# esp-sensor_01.net
KiCad netlist of a schematic drawn in EAGLE
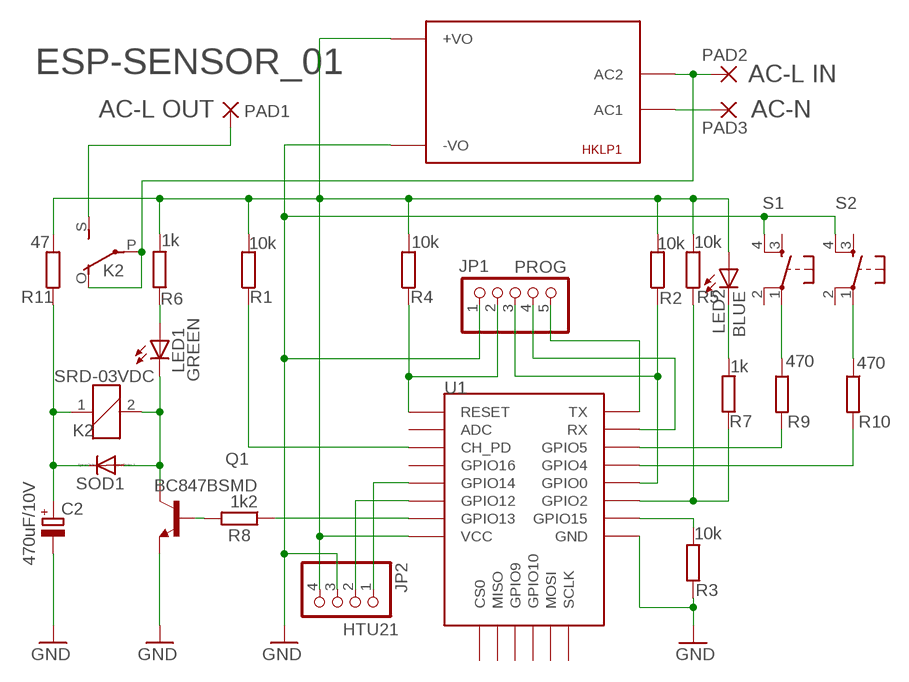
[diagram p0: schematic, sheet 1]

(export (version "E")
  (design (tool "Eeschema 10.0.6"))
  (components
    (comp (ref "C2")
      (value "470uF/10V")
      (footprint "eagle-import:E3,5-8-B")
      (libsource (lib "eagle-import") (part "CPOL-EUE3,5-8-B"))
    )
    (comp (ref "HKLP1")
      (value "HKLPM01")
      (footprint "eagle-import:HKLPM01")
      (libsource (lib "eagle-import") (part "HKLPM01"))
    )
    (comp (ref "JP1")
      (value "PROG")
      (footprint "eagle-import:1X05-2B")
      (libsource (lib "eagle-import") (part "PINHD-1X51X05-2B"))
    )
    (comp (ref "JP2")
      (value "HTU21")
      (footprint "eagle-import:1X04")
      (libsource (lib "eagle-import") (part "PINHD-1X4"))
    )
    (comp (ref "K2")
      (value "SRD-03VDC")
      (footprint "eagle-import:G5L-2B")
      (libsource (lib "eagle-import") (part "G5L-2B"))
    )
    (comp (ref "LED1")
      (value "GREEN")
      (footprint "eagle-import:LED3MM-B")
      (libsource (lib "eagle-import") (part "LEDB"))
    )
    (comp (ref "LED2")
      (value "BLUE")
      (footprint "eagle-import:LED3MM-B")
      (libsource (lib "eagle-import") (part "LEDB"))
    )
    (comp (ref "PAD1")
      (value "3,17/1,1")
      (footprint "eagle-import:3,17_1,1")
      (libsource (lib "eagle-import") (part "3,17/1,1"))
    )
    (comp (ref "PAD2")
      (value "3,17/1,1")
      (footprint "eagle-import:3,17_1,1")
      (libsource (lib "eagle-import") (part "3,17/1,1"))
    )
    (comp (ref "PAD3")
      (value "3,17/1,1")
      (footprint "eagle-import:3,17_1,1")
      (libsource (lib "eagle-import") (part "3,17/1,1"))
    )
    (comp (ref "Q1")
      (value "BC847BSMD")
      (footprint "eagle-import:SOT23")
      (libsource (lib "eagle-import") (part "BC847SMDB"))
    )
    (comp (ref "R1")
      (value "10k")
      (footprint "eagle-import:M1206")
      (libsource (lib "eagle-import") (part "R-EU_M1206"))
    )
    (comp (ref "R2")
      (value "10k")
      (footprint "eagle-import:M1206")
      (libsource (lib "eagle-import") (part "R-EU_M1206"))
    )
    (comp (ref "R3")
      (value "10k")
      (footprint "eagle-import:M1206")
      (libsource (lib "eagle-import") (part "R-EU_M1206"))
    )
    (comp (ref "R4")
      (value "10k")
      (footprint "eagle-import:M1206")
      (libsource (lib "eagle-import") (part "R-EU_M1206"))
    )
    (comp (ref "R5")
      (value "10k")
      (footprint "eagle-import:M1206")
      (libsource (lib "eagle-import") (part "R-EU_M1206"))
    )
    (comp (ref "R6")
      (value "1k")
      (footprint "eagle-import:M1206")
      (libsource (lib "eagle-import") (part "R-EU_M1206"))
    )
    (comp (ref "R7")
      (value "1k")
      (footprint "eagle-import:M1206")
      (libsource (lib "eagle-import") (part "R-EU_M1206"))
    )
    (comp (ref "R8")
      (value "1k2")
      (footprint "eagle-import:M1206")
      (libsource (lib "eagle-import") (part "R-EU_M1206"))
    )
    (comp (ref "R9")
      (value "470")
      (footprint "eagle-import:M1206")
      (libsource (lib "eagle-import") (part "R-EU_M1206"))
    )
    (comp (ref "R10")
      (value "470")
      (footprint "eagle-import:M1206")
      (libsource (lib "eagle-import") (part "R-EU_M1206"))
    )
    (comp (ref "R11")
      (value "47")
      (footprint "eagle-import:0207_10-2B")
      (libsource (lib "eagle-import") (part "R-EU_0207/10-2B"))
    )
    (comp (ref "S1")
      (value "DTS-6-B")
      (footprint "eagle-import:DTS-6-B")
      (libsource (lib "eagle-import") (part "DTS-6-B"))
    )
    (comp (ref "S2")
      (value "DTS-6-B")
      (footprint "eagle-import:DTS-6-B")
      (libsource (lib "eagle-import") (part "DTS-6-B"))
    )
    (comp (ref "SOD1")
      (value "DIODE-MELF-MLL41")
      (footprint "eagle-import:MELF-MLL41")
      (libsource (lib "eagle-import") (part "DIODE-MELF-MLL41"))
    )
    (comp (ref "U1")
      (value "ESP12ESMD")
      (footprint "eagle-import:ESP12E-SMD")
      (libsource (lib "eagle-import") (part "ESP12ESMD"))
    )
  )
  (nets
    (net (code "1") (name "GND") (class "Default")
      (node (ref "C2") (pin "-") (pinfunction "-_-") (pintype "passive"))
      (node (ref "HKLP1") (pin "P$3") (pinfunction "-VO_P$3") (pintype "output"))
      (node (ref "JP1") (pin "1") (pinfunction "1_1") (pintype "passive"))
      (node (ref "JP2") (pin "3") (pinfunction "3_3") (pintype "passive"))
      (node (ref "Q1") (pin "2") (pinfunction "E_2") (pintype "passive"))
      (node (ref "R3") (pin "1") (pinfunction "1_1") (pintype "passive"))
      (node (ref "S1") (pin "4") (pinfunction "4_4") (pintype "passive"))
      (node (ref "S2") (pin "4") (pinfunction "4_4") (pintype "passive"))
      (node (ref "U1") (pin "GND") (pinfunction "GND_GND") (pintype "bidirectional"))
    )
    (net (code "2") (name "Net-(C2-Pad+)") (class "Default")
      (node (ref "C2") (pin "+") (pinfunction "+_+") (pintype "passive"))
      (node (ref "K2") (pin "1") (pinfunction "1_1") (pintype "passive"))
      (node (ref "R11") (pin "1") (pinfunction "1_1") (pintype "passive"))
      (node (ref "SOD1") (pin "C") (pinfunction "C_C") (pintype "passive"))
    )
    (net (code "3") (name "Net-(HKLP1-+VO)") (class "Default")
      (node (ref "HKLP1") (pin "P$4") (pinfunction "+VO_P$4") (pintype "output"))
      (node (ref "JP2") (pin "4") (pinfunction "4_4") (pintype "passive"))
      (node (ref "LED2") (pin "A") (pinfunction "A_A") (pintype "passive"))
      (node (ref "R1") (pin "2") (pinfunction "2_2") (pintype "passive"))
      (node (ref "R11") (pin "2") (pinfunction "2_2") (pintype "passive"))
      (node (ref "R2") (pin "2") (pinfunction "2_2") (pintype "passive"))
      (node (ref "R4") (pin "2") (pinfunction "2_2") (pintype "passive"))
      (node (ref "R5") (pin "2") (pinfunction "2_2") (pintype "passive"))
      (node (ref "R6") (pin "2") (pinfunction "2_2") (pintype "passive"))
      (node (ref "U1") (pin "VCC") (pinfunction "VCC_VCC") (pintype "bidirectional"))
    )
    (net (code "4") (name "Net-(HKLP1-AC1)") (class "Default")
      (node (ref "HKLP1") (pin "P$1") (pinfunction "AC1_P$1") (pintype "power_in"))
      (node (ref "PAD3") (pin "1") (pinfunction "P_1") (pintype "passive"))
    )
    (net (code "5") (name "Net-(HKLP1-AC2)") (class "Default")
      (node (ref "HKLP1") (pin "P$2") (pinfunction "AC2_P$2") (pintype "power_in"))
      (node (ref "K2") (pin "O") (pinfunction "O_O") (pintype "passive"))
      (node (ref "K2") (pin "P") (pinfunction "P_P") (pintype "passive"))
      (node (ref "PAD2") (pin "1") (pinfunction "P_1") (pintype "passive"))
    )
    (net (code "6") (name "Net-(JP1-Pad2)") (class "Default")
      (node (ref "JP1") (pin "2") (pinfunction "2_2") (pintype "passive"))
      (node (ref "R4") (pin "1") (pinfunction "1_1") (pintype "passive"))
      (node (ref "U1") (pin "RESET") (pinfunction "RESET_RESET") (pintype "bidirectional"))
    )
    (net (code "7") (name "Net-(JP1-Pad3)") (class "Default")
      (node (ref "JP1") (pin "3") (pinfunction "3_3") (pintype "passive"))
      (node (ref "R2") (pin "1") (pinfunction "1_1") (pintype "passive"))
      (node (ref "U1") (pin "GPIO0") (pinfunction "GPIO0_GPIO0") (pintype "bidirectional"))
    )
    (net (code "8") (name "Net-(JP2-Pad1)") (class "Default")
      (node (ref "JP2") (pin "1") (pinfunction "1_1") (pintype "passive"))
      (node (ref "U1") (pin "GPIO14") (pinfunction "GPIO14_GPIO14") (pintype "bidirectional"))
    )
    (net (code "9") (name "Net-(JP2-Pad2)") (class "Default")
      (node (ref "JP2") (pin "2") (pinfunction "2_2") (pintype "passive"))
      (node (ref "U1") (pin "GPIO12") (pinfunction "GPIO12_GPIO12") (pintype "bidirectional"))
    )
    (net (code "10") (name "Net-(LED1-C)") (class "Default")
      (node (ref "K2") (pin "2") (pinfunction "2_2") (pintype "passive"))
      (node (ref "LED1") (pin "K") (pinfunction "C_K") (pintype "passive"))
      (node (ref "Q1") (pin "3") (pinfunction "C_3") (pintype "passive"))
      (node (ref "SOD1") (pin "A") (pinfunction "A_A") (pintype "passive"))
    )
    (net (code "11") (name "Net-(LED1-PadA)") (class "Default")
      (node (ref "LED1") (pin "A") (pinfunction "A_A") (pintype "passive"))
      (node (ref "R6") (pin "1") (pinfunction "1_1") (pintype "passive"))
    )
    (net (code "12") (name "Net-(LED2-C)") (class "Default")
      (node (ref "LED2") (pin "K") (pinfunction "C_K") (pintype "passive"))
      (node (ref "R7") (pin "2") (pinfunction "2_2") (pintype "passive"))
    )
    (net (code "13") (name "Net-(PAD1-P)") (class "Default")
      (node (ref "K2") (pin "S") (pinfunction "S_S") (pintype "passive"))
      (node (ref "PAD1") (pin "1") (pinfunction "P_1") (pintype "passive"))
    )
    (net (code "14") (name "Net-(Q1-B)") (class "Default")
      (node (ref "Q1") (pin "1") (pinfunction "B_1") (pintype "passive"))
      (node (ref "R8") (pin "2") (pinfunction "2_2") (pintype "passive"))
    )
    (net (code "15") (name "Net-(R1-Pad1)") (class "Default")
      (node (ref "R1") (pin "1") (pinfunction "1_1") (pintype "passive"))
      (node (ref "U1") (pin "CH_PD") (pinfunction "CH_PD_CH_PD") (pintype "bidirectional"))
    )
    (net (code "16") (name "Net-(R3-Pad2)") (class "Default")
      (node (ref "R3") (pin "2") (pinfunction "2_2") (pintype "passive"))
      (node (ref "U1") (pin "GPIO15") (pinfunction "GPIO15_GPIO15") (pintype "bidirectional"))
    )
    (net (code "17") (name "Net-(R5-Pad1)") (class "Default")
      (node (ref "R5") (pin "1") (pinfunction "1_1") (pintype "passive"))
      (node (ref "R7") (pin "1") (pinfunction "1_1") (pintype "passive"))
      (node (ref "U1") (pin "GPIO2") (pinfunction "GPIO2_GPIO2") (pintype "bidirectional"))
    )
    (net (code "18") (name "Net-(R8-Pad1)") (class "Default")
      (node (ref "R8") (pin "1") (pinfunction "1_1") (pintype "passive"))
      (node (ref "U1") (pin "GPIO13") (pinfunction "GPIO13_GPIO13") (pintype "bidirectional"))
    )
    (net (code "19") (name "Net-(R9-Pad1)") (class "Default")
      (node (ref "R9") (pin "1") (pinfunction "1_1") (pintype "passive"))
      (node (ref "S1") (pin "1") (pinfunction "1_1") (pintype "passive"))
    )
    (net (code "20") (name "Net-(R9-Pad2)") (class "Default")
      (node (ref "R9") (pin "2") (pinfunction "2_2") (pintype "passive"))
      (node (ref "U1") (pin "GPIO5") (pinfunction "GPIO5_GPIO5") (pintype "bidirectional"))
    )
    (net (code "21") (name "Net-(R10-Pad1)") (class "Default")
      (node (ref "R10") (pin "1") (pinfunction "1_1") (pintype "passive"))
      (node (ref "S2") (pin "1") (pinfunction "1_1") (pintype "passive"))
    )
    (net (code "22") (name "Net-(R10-Pad2)") (class "Default")
      (node (ref "R10") (pin "2") (pinfunction "2_2") (pintype "passive"))
      (node (ref "U1") (pin "GPIO4") (pinfunction "GPIO4_GPIO4") (pintype "bidirectional"))
    )
    (net (code "23") (name "Net-(U1-RX)") (class "Default")
      (node (ref "JP1") (pin "4") (pinfunction "4_4") (pintype "passive"))
      (node (ref "U1") (pin "RXD0") (pinfunction "RX_RXD0") (pintype "bidirectional"))
    )
    (net (code "24") (name "Net-(U1-TX)") (class "Default")
      (node (ref "JP1") (pin "5") (pinfunction "5_5") (pintype "passive"))
      (node (ref "U1") (pin "TXD0") (pinfunction "TX_TXD0") (pintype "bidirectional"))
    )
    (net (code "25") (name "unconnected-(S1-Pad2)") (class "Default")
      (node (ref "S1") (pin "2") (pinfunction "2_2") (pintype "passive"))
    )
    (net (code "26") (name "unconnected-(S1-Pad3)") (class "Default")
      (node (ref "S1") (pin "3") (pinfunction "3_3") (pintype "passive"))
    )
    (net (code "27") (name "unconnected-(S2-Pad2)") (class "Default")
      (node (ref "S2") (pin "2") (pinfunction "2_2") (pintype "passive"))
    )
    (net (code "28") (name "unconnected-(S2-Pad3)") (class "Default")
      (node (ref "S2") (pin "3") (pinfunction "3_3") (pintype "passive"))
    )
    (net (code "29") (name "unconnected-(U1-PadADC)") (class "Default")
      (node (ref "U1") (pin "ADC") (pinfunction "ADC_ADC") (pintype "bidirectional"))
    )
    (net (code "30") (name "unconnected-(U1-PadCS0)") (class "Default")
      (node (ref "U1") (pin "CS0") (pinfunction "CS0_CS0") (pintype "bidirectional"))
    )
    (net (code "31") (name "unconnected-(U1-PadGPIO9)") (class "Default")
      (node (ref "U1") (pin "GPIO9") (pinfunction "GPIO9_GPIO9") (pintype "bidirectional"))
    )
    (net (code "32") (name "unconnected-(U1-PadGPIO10)") (class "Default")
      (node (ref "U1") (pin "GPIO10") (pinfunction "GPIO10_GPIO10") (pintype "bidirectional"))
    )
    (net (code "33") (name "unconnected-(U1-PadGPIO16)") (class "Default")
      (node (ref "U1") (pin "GPIO16") (pinfunction "GPIO16_GPIO16") (pintype "bidirectional"))
    )
    (net (code "34") (name "unconnected-(U1-PadMISO)") (class "Default")
      (node (ref "U1") (pin "MISO") (pinfunction "MISO_MISO") (pintype "bidirectional"))
    )
    (net (code "35") (name "unconnected-(U1-PadMOSI)") (class "Default")
      (node (ref "U1") (pin "MOSI") (pinfunction "MOSI_MOSI") (pintype "bidirectional"))
    )
    (net (code "36") (name "unconnected-(U1-PadSCLK)") (class "Default")
      (node (ref "U1") (pin "SCLK") (pinfunction "SCLK_SCLK") (pintype "bidirectional"))
    )
  )
)
